# Simple-Charger-LiIon-OpampBased-LM324.net
KiCad netlist of a schematic drawn in EAGLE
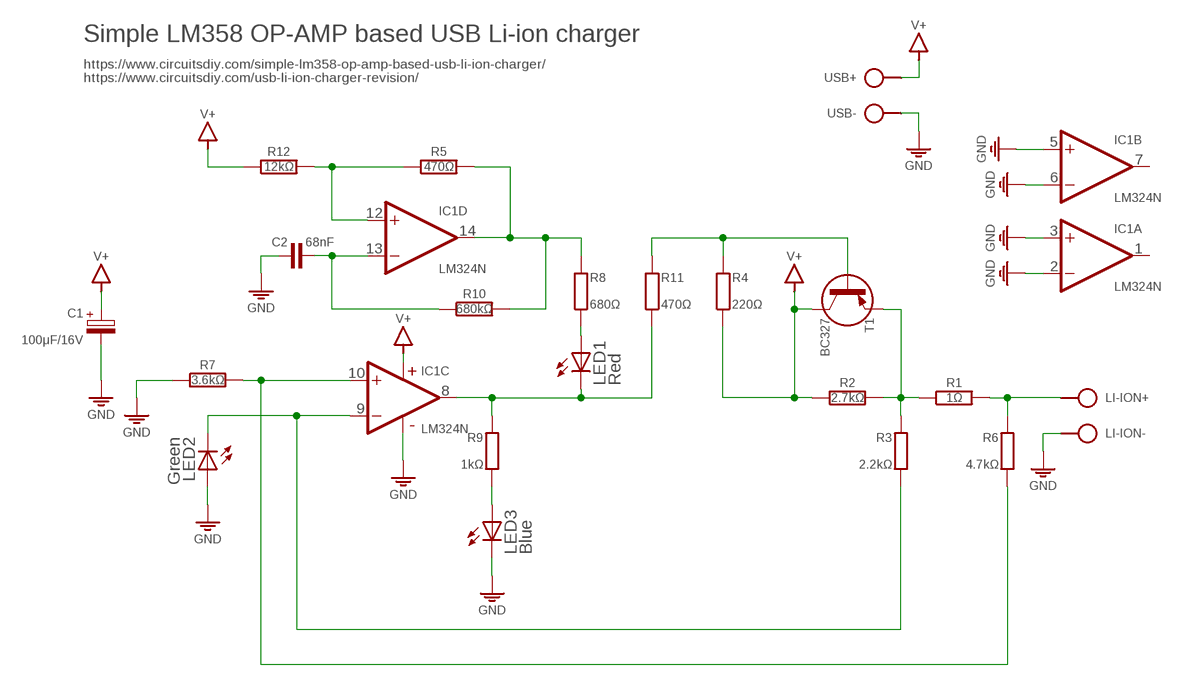
[diagram p0: schematic, sheet 1]

(export (version "E")
  (design (tool "Eeschema 10.0.6"))
  (components
    (comp (ref "C1")
      (value "100μF/16V")
      (footprint "eagle-import:E2,5-5_V")
      (libsource (lib "eagle-import") (part "CPOLE2,5-5/V"))
    )
    (comp (ref "C2")
      (value "68nF")
      (footprint "eagle-import:C050-020X044_V")
      (libsource (lib "eagle-import") (part "C-H050-020X044/V"))
    )
    (comp (ref "IC1")
      (value "LM324N")
      (footprint "eagle-import:DIL14")
      (libsource (lib "eagle-import") (part "LM324N"))
    )
    (comp (ref "LED1")
      (value "Red")
      (footprint "eagle-import:LED3MM")
      (libsource (lib "eagle-import") (part "LED3MM"))
    )
    (comp (ref "LED2")
      (value "Green")
      (footprint "eagle-import:LED3MM")
      (libsource (lib "eagle-import") (part "LED3MM"))
    )
    (comp (ref "LED3")
      (value "Blue")
      (footprint "eagle-import:LED3MM")
      (libsource (lib "eagle-import") (part "LED3MM"))
    )
    (comp (ref "LI-ION")
      (value "SPAD+-+-")
      (footprint "eagle-import:SPAD+-")
      (libsource (lib "eagle-import") (part "SPAD+-+-"))
    )
    (comp (ref "R1")
      (value "1Ω")
      (footprint "eagle-import:0204_10-V")
      (libsource (lib "eagle-import") (part "R-H0204/10-V"))
    )
    (comp (ref "R2")
      (value "2.7kΩ")
      (footprint "eagle-import:0204_10-V")
      (libsource (lib "eagle-import") (part "R-H0204/10-V"))
    )
    (comp (ref "R3")
      (value "2.2kΩ")
      (footprint "eagle-import:0204_10-V")
      (libsource (lib "eagle-import") (part "R0204/10-V"))
    )
    (comp (ref "R4")
      (value "220Ω")
      (footprint "eagle-import:0204_10")
      (libsource (lib "eagle-import") (part "R0204/10"))
    )
    (comp (ref "R5")
      (value "470Ω")
      (footprint "eagle-import:0204_10")
      (libsource (lib "eagle-import") (part "R-H0204/10"))
    )
    (comp (ref "R6")
      (value "4.7kΩ")
      (footprint "eagle-import:0204_10-V")
      (libsource (lib "eagle-import") (part "R0204/10-V"))
    )
    (comp (ref "R7")
      (value "3.6kΩ")
      (footprint "eagle-import:0204_10-V")
      (libsource (lib "eagle-import") (part "R-H0204/10-V"))
    )
    (comp (ref "R8")
      (value "680Ω")
      (footprint "eagle-import:0204_10")
      (libsource (lib "eagle-import") (part "R0204/10"))
    )
    (comp (ref "R9")
      (value "1kΩ")
      (footprint "eagle-import:0204_10-V")
      (libsource (lib "eagle-import") (part "R0204/10-V"))
    )
    (comp (ref "R10")
      (value "680kΩ")
      (footprint "eagle-import:0204_2V")
      (libsource (lib "eagle-import") (part "R-H0204/2V"))
    )
    (comp (ref "R11")
      (value "470Ω")
      (footprint "eagle-import:0204_10-V")
      (libsource (lib "eagle-import") (part "R0204/10-V"))
    )
    (comp (ref "R12")
      (value "12kΩ")
      (footprint "eagle-import:0204_10-V")
      (libsource (lib "eagle-import") (part "R-H0204/10-V"))
    )
    (comp (ref "T1")
      (value "BC327")
      (footprint "eagle-import:TO92")
      (libsource (lib "eagle-import") (part "BC327"))
    )
    (comp (ref "USB")
      (value "SPAD+--+")
      (footprint "eagle-import:SPAD-+")
      (libsource (lib "eagle-import") (part "SPAD+--+"))
    )
  )
  (nets
    (net (code "1") (name "GND") (class "Default")
      (node (ref "C1") (pin "-") (pinfunction "-_-") (pintype "passive"))
      (node (ref "C2") (pin "1") (pinfunction "1_1") (pintype "passive"))
      (node (ref "IC1") (pin "11") (pinfunction "V-_11") (pintype "power_in"))
      (node (ref "IC1") (pin "2") (pinfunction "-IN_2") (pintype "input"))
      (node (ref "IC1") (pin "3") (pinfunction "+IN_3") (pintype "input"))
      (node (ref "IC1") (pin "5") (pinfunction "+IN_5") (pintype "input"))
      (node (ref "IC1") (pin "6") (pinfunction "-IN_6") (pintype "input"))
      (node (ref "LED2") (pin "A") (pinfunction "A_A") (pintype "passive"))
      (node (ref "LED3") (pin "K") (pinfunction "C_K") (pintype "passive"))
      (node (ref "LI-ION") (pin "1") (pinfunction "P$1_1") (pintype "passive"))
      (node (ref "R7") (pin "1") (pinfunction "1_1") (pintype "passive"))
      (node (ref "USB") (pin "1") (pinfunction "P$1_1") (pintype "passive"))
    )
    (net (code "2") (name "Net-(IC1C-+IN)") (class "Default")
      (node (ref "IC1") (pin "10") (pinfunction "+IN_10") (pintype "input"))
      (node (ref "R6") (pin "2") (pinfunction "2_2") (pintype "passive"))
      (node (ref "R7") (pin "2") (pinfunction "2_2") (pintype "passive"))
    )
    (net (code "3") (name "Net-(IC1C--IN)") (class "Default")
      (node (ref "IC1") (pin "9") (pinfunction "-IN_9") (pintype "input"))
      (node (ref "LED2") (pin "K") (pinfunction "C_K") (pintype "passive"))
      (node (ref "R3") (pin "2") (pinfunction "2_2") (pintype "passive"))
    )
    (net (code "4") (name "Net-(IC1C-OUT)") (class "Default")
      (node (ref "IC1") (pin "8") (pinfunction "OUT_8") (pintype "output"))
      (node (ref "LED1") (pin "K") (pinfunction "C_K") (pintype "passive"))
      (node (ref "R11") (pin "2") (pinfunction "2_2") (pintype "passive"))
      (node (ref "R9") (pin "1") (pinfunction "1_1") (pintype "passive"))
    )
    (net (code "5") (name "Net-(IC1D-+IN)") (class "Default")
      (node (ref "IC1") (pin "12") (pinfunction "+IN_12") (pintype "input"))
      (node (ref "R12") (pin "2") (pinfunction "2_2") (pintype "passive"))
      (node (ref "R5") (pin "1") (pinfunction "1_1") (pintype "passive"))
    )
    (net (code "6") (name "Net-(IC1D--IN)") (class "Default")
      (node (ref "C2") (pin "2") (pinfunction "2_2") (pintype "passive"))
      (node (ref "IC1") (pin "13") (pinfunction "-IN_13") (pintype "input"))
      (node (ref "R10") (pin "1") (pinfunction "1_1") (pintype "passive"))
    )
    (net (code "7") (name "Net-(IC1D-OUT)") (class "Default")
      (node (ref "IC1") (pin "14") (pinfunction "OUT_14") (pintype "output"))
      (node (ref "R10") (pin "2") (pinfunction "2_2") (pintype "passive"))
      (node (ref "R5") (pin "2") (pinfunction "2_2") (pintype "passive"))
      (node (ref "R8") (pin "1") (pinfunction "1_1") (pintype "passive"))
    )
    (net (code "8") (name "Net-(LED1-PadA)") (class "Default")
      (node (ref "LED1") (pin "A") (pinfunction "A_A") (pintype "passive"))
      (node (ref "R8") (pin "2") (pinfunction "2_2") (pintype "passive"))
    )
    (net (code "9") (name "Net-(LED3-PadA)") (class "Default")
      (node (ref "LED3") (pin "A") (pinfunction "A_A") (pintype "passive"))
      (node (ref "R9") (pin "2") (pinfunction "2_2") (pintype "passive"))
    )
    (net (code "10") (name "Net-(LI-IONA-P$1)") (class "Default")
      (node (ref "LI-ION") (pin "2") (pinfunction "P$1_2") (pintype "passive"))
      (node (ref "R1") (pin "2") (pinfunction "2_2") (pintype "passive"))
      (node (ref "R6") (pin "1") (pinfunction "1_1") (pintype "passive"))
    )
    (net (code "11") (name "Net-(T1-B)") (class "Default")
      (node (ref "R11") (pin "1") (pinfunction "1_1") (pintype "passive"))
      (node (ref "R4") (pin "1") (pinfunction "1_1") (pintype "passive"))
      (node (ref "T1") (pin "2") (pinfunction "B_2") (pintype "passive"))
    )
    (net (code "12") (name "Net-(T1-E)") (class "Default")
      (node (ref "R1") (pin "1") (pinfunction "1_1") (pintype "passive"))
      (node (ref "R2") (pin "2") (pinfunction "2_2") (pintype "passive"))
      (node (ref "R3") (pin "1") (pinfunction "1_1") (pintype "passive"))
      (node (ref "T1") (pin "3") (pinfunction "E_3") (pintype "passive"))
    )
    (net (code "13") (name "V+") (class "Default")
      (node (ref "C1") (pin "+") (pinfunction "+_+") (pintype "passive"))
      (node (ref "IC1") (pin "4") (pinfunction "V+_4") (pintype "power_in"))
      (node (ref "R12") (pin "1") (pinfunction "1_1") (pintype "passive"))
      (node (ref "R2") (pin "1") (pinfunction "1_1") (pintype "passive"))
      (node (ref "R4") (pin "2") (pinfunction "2_2") (pintype "passive"))
      (node (ref "T1") (pin "1") (pinfunction "C_1") (pintype "passive"))
      (node (ref "USB") (pin "2") (pinfunction "P$1_2") (pintype "passive"))
    )
    (net (code "14") (name "unconnected-(IC1A-OUT-Pad1)") (class "Default")
      (node (ref "IC1") (pin "1") (pinfunction "OUT_1") (pintype "output"))
    )
    (net (code "15") (name "unconnected-(IC1B-OUT-Pad7)") (class "Default")
      (node (ref "IC1") (pin "7") (pinfunction "OUT_7") (pintype "output"))
    )
  )
)
